# Enc28j60.net
KiCad netlist of a schematic drawn in Altium Designer
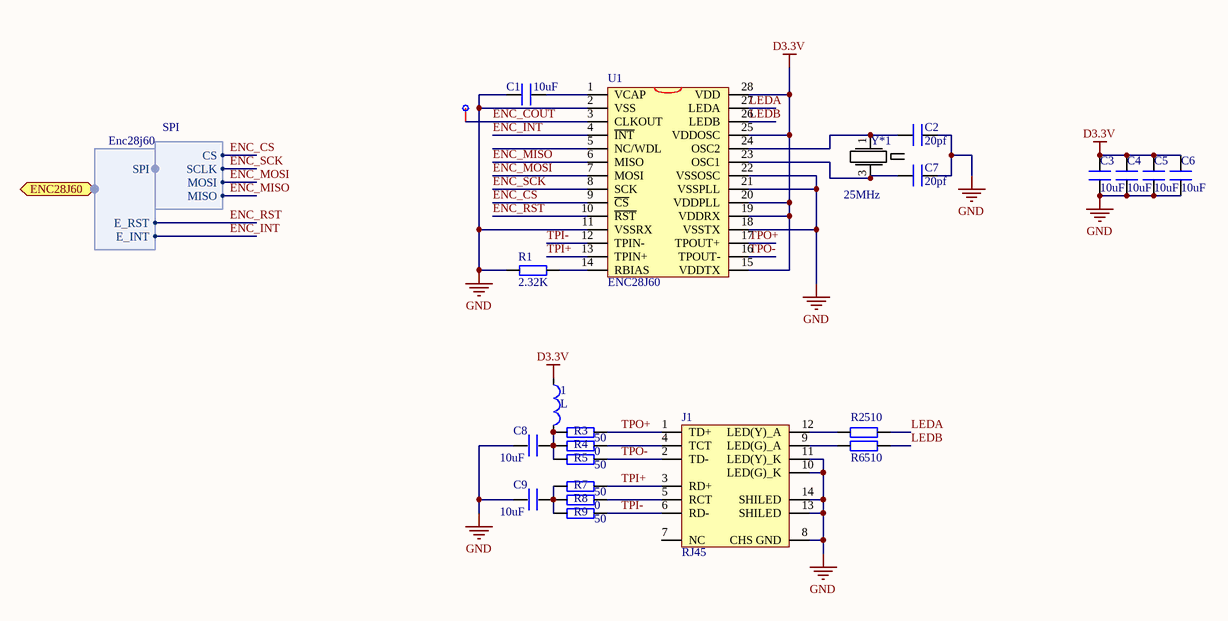
[diagram p0: Enc28j60.SchDoc]

(export (version "E")
  (design (tool "Eeschema 10.0.6"))
  (components
    (comp (ref "*1") (value "Point") (footprint "Point") (libsource (lib "authuir") (part "Point")))
    (comp (ref "1") (value "L") (footprint "0805") (libsource (lib "authuir") (part "L")))
    (comp (ref "C1") (value "10uF") (footprint "0805") (libsource (lib "ENC28J60网络模块封装库") (part "C")))
    (comp (ref "C2") (value "20pf") (footprint "0603P") (libsource (lib "ENC28J60网络模块_SCH") (part "C")))
    (comp (ref "C3") (value "10uF") (footprint "0603P") (libsource (lib "ENC28J60网络模块封装库") (part "C")))
    (comp (ref "C4") (value "10uF") (footprint "0603P") (libsource (lib "ENC28J60网络模块封装库") (part "C")))
    (comp (ref "C5") (value "10uF") (footprint "0603P") (libsource (lib "ENC28J60网络模块封装库") (part "C")))
    (comp (ref "C6") (value "10uF") (footprint "0603P") (libsource (lib "ENC28J60网络模块封装库") (part "C")))
    (comp (ref "C7") (value "20pf") (footprint "0603P") (libsource (lib "ENC28J60网络模块_SCH") (part "C")))
    (comp (ref "C8") (value "10uF") (footprint "0603P") (libsource (lib "ENC28J60网络模块封装库") (part "C")))
    (comp (ref "C9") (value "10uF") (footprint "0603P") (libsource (lib "ENC28J60网络模块封装库") (part "C")))
    (comp (ref "J1")
      (value "RJ45")
      (footprint "HR911105A")
      (libsource (lib "ENC28J60网络模块封装库") (part "HR911105"))
    )
    (comp (ref "R1") (value "2.32K") (footprint "0603P") (libsource (lib "ENC28J60网络模块封装库") (part "R")))
    (comp (ref "R2") (value "510") (footprint "0603P") (libsource (lib "ENC28J60网络模块封装库") (part "R")))
    (comp (ref "R3") (value "50") (footprint "0603P") (libsource (lib "ENC28J60网络模块封装库") (part "R")))
    (comp (ref "R4") (value "0") (footprint "0603P") (libsource (lib "ENC28J60网络模块封装库") (part "R")))
    (comp (ref "R5") (value "50") (footprint "0603P") (libsource (lib "ENC28J60网络模块封装库") (part "R")))
    (comp (ref "R6") (value "510") (footprint "0603P") (libsource (lib "ENC28J60网络模块封装库") (part "R")))
    (comp (ref "R7") (value "50") (footprint "0603P") (libsource (lib "ENC28J60网络模块封装库") (part "R")))
    (comp (ref "R8") (value "0") (footprint "0603P") (libsource (lib "ENC28J60网络模块封装库") (part "R")))
    (comp (ref "R9") (value "50") (footprint "0603P") (libsource (lib "ENC28J60网络模块封装库") (part "R")))
    (comp (ref "U1")
      (value "ENC28J60")
      (footprint "SSOP28")
      (libsource (lib "ENC28J60网络模块_SCH") (part "ENC28J60"))
    )
    (comp (ref "Y*1") (value "25MHz") (footprint "4脚晶振") (libsource (lib "authuir") (part "XTAL_16M")))
  )
  (nets
    (net (code "2") (name "/ENC_COUT") (class "Default")
      (node (ref "*1") (pin "1") (pinfunction "Point_1") (pintype "passive"))
      (node (ref "U1") (pin "3") (pinfunction "CLKOUT_3") (pintype "passive"))
    )
    (net (code "3") (name "/ENC_CS") (class "Default")
      (node (ref "U1") (pin "9") (pinfunction "~{CS}_9") (pintype "passive"))
    )
    (net (code "4") (name "/ENC_INT") (class "Default")
      (node (ref "U1") (pin "4") (pinfunction "~{INT}_4") (pintype "passive"))
    )
    (net (code "5") (name "/ENC_MISO") (class "Default")
      (node (ref "U1") (pin "6") (pinfunction "MISO_6") (pintype "passive"))
    )
    (net (code "6") (name "/ENC_MOSI") (class "Default")
      (node (ref "U1") (pin "7") (pinfunction "MOSI_7") (pintype "passive"))
    )
    (net (code "7") (name "/ENC_RST") (class "Default")
      (node (ref "U1") (pin "10") (pinfunction "~{RST}_10") (pintype "passive"))
    )
    (net (code "8") (name "/ENC_SCK") (class "Default")
      (node (ref "U1") (pin "8") (pinfunction "SCK_8") (pintype "passive"))
    )
    (net (code "9") (name "/LEDA") (class "Default")
      (node (ref "R2") (pin "2") (pintype "passive"))
      (node (ref "U1") (pin "27") (pinfunction "LEDA_27") (pintype "passive"))
    )
    (net (code "10") (name "/LEDB") (class "Default")
      (node (ref "R6") (pin "2") (pintype "passive"))
      (node (ref "U1") (pin "26") (pinfunction "LEDB_26") (pintype "passive"))
    )
    (net (code "11") (name "/TPI+") (class "Default")
      (node (ref "J1") (pin "3") (pinfunction "RD+_3") (pintype "passive"))
      (node (ref "R7") (pin "2") (pintype "passive"))
      (node (ref "U1") (pin "13") (pinfunction "TPIN+_13") (pintype "passive"))
    )
    (net (code "12") (name "/TPI-") (class "Default")
      (node (ref "J1") (pin "6") (pinfunction "RD-_6") (pintype "passive"))
      (node (ref "R9") (pin "2") (pintype "passive"))
      (node (ref "U1") (pin "12") (pinfunction "TPIN-_12") (pintype "passive"))
    )
    (net (code "13") (name "/TPO+") (class "Default")
      (node (ref "J1") (pin "1") (pinfunction "TD+_1") (pintype "passive"))
      (node (ref "R3") (pin "2") (pintype "passive"))
      (node (ref "U1") (pin "17") (pinfunction "TPOUT+_17") (pintype "passive"))
    )
    (net (code "14") (name "/TPO-") (class "Default")
      (node (ref "J1") (pin "2") (pinfunction "TD-_2") (pintype "passive"))
      (node (ref "R5") (pin "2") (pintype "passive"))
      (node (ref "U1") (pin "16") (pinfunction "TPOUT-_16") (pintype "passive"))
    )
    (net (code "16") (name "D3.3V") (class "Default")
      (node (ref "1") (pin "2") (pinfunction "2_2") (pintype "passive"))
      (node (ref "C3") (pin "2") (pintype "passive"))
      (node (ref "C4") (pin "2") (pintype "passive"))
      (node (ref "C5") (pin "2") (pintype "passive"))
      (node (ref "C6") (pin "2") (pintype "passive"))
      (node (ref "U1") (pin "15") (pinfunction "VDDTX_15") (pintype "passive"))
      (node (ref "U1") (pin "19") (pinfunction "VDDRX_19") (pintype "passive"))
      (node (ref "U1") (pin "20") (pinfunction "VDDPLL_20") (pintype "passive"))
      (node (ref "U1") (pin "25") (pinfunction "VDDOSC_25") (pintype "passive"))
      (node (ref "U1") (pin "28") (pinfunction "VDD_28") (pintype "passive"))
    )
    (net (code "17") (name "GND") (class "Default")
      (node (ref "C1") (pin "1") (pintype "passive"))
      (node (ref "C2") (pin "2") (pintype "passive"))
      (node (ref "C3") (pin "1") (pintype "passive"))
      (node (ref "C4") (pin "1") (pintype "passive"))
      (node (ref "C5") (pin "1") (pintype "passive"))
      (node (ref "C6") (pin "1") (pintype "passive"))
      (node (ref "C7") (pin "2") (pintype "passive"))
      (node (ref "C8") (pin "1") (pintype "passive"))
      (node (ref "C9") (pin "1") (pintype "passive"))
      (node (ref "J1") (pin "10") (pinfunction "LED(G)_K_10") (pintype "passive"))
      (node (ref "J1") (pin "11") (pinfunction "LED(Y)_K_11") (pintype "passive"))
      (node (ref "J1") (pin "13") (pinfunction "SHILED_13") (pintype "passive"))
      (node (ref "J1") (pin "14") (pinfunction "SHILED_14") (pintype "passive"))
      (node (ref "J1") (pin "8") (pinfunction "CHS_GND_8") (pintype "passive"))
      (node (ref "R1") (pin "1") (pintype "passive"))
      (node (ref "U1") (pin "11") (pinfunction "VSSRX_11") (pintype "passive"))
      (node (ref "U1") (pin "18") (pinfunction "VSSTX_18") (pintype "passive"))
      (node (ref "U1") (pin "2") (pinfunction "VSS_2") (pintype "passive"))
      (node (ref "U1") (pin "21") (pinfunction "VSSPLL_21") (pintype "passive"))
      (node (ref "U1") (pin "22") (pinfunction "VSSOSC_22") (pintype "passive"))
    )
    (net (code "18") (name "Net-(1-Pad1)") (class "Default")
      (node (ref "1") (pin "1") (pinfunction "1_1") (pintype "passive"))
      (node (ref "C8") (pin "2") (pintype "passive"))
      (node (ref "R3") (pin "1") (pintype "passive"))
      (node (ref "R4") (pin "1") (pintype "passive"))
      (node (ref "R5") (pin "1") (pintype "passive"))
    )
    (net (code "19") (name "Net-(C9-Pad2)") (class "Default")
      (node (ref "C9") (pin "2") (pintype "passive"))
      (node (ref "R7") (pin "1") (pintype "passive"))
      (node (ref "R8") (pin "1") (pintype "passive"))
      (node (ref "R9") (pin "1") (pintype "passive"))
    )
    (net (code "20") (name "Net-(J1-LED(G)_A)") (class "Default")
      (node (ref "J1") (pin "9") (pinfunction "LED(G)_A_9") (pintype "passive"))
      (node (ref "R6") (pin "1") (pintype "passive"))
    )
    (net (code "21") (name "Net-(J1-LED(Y)_A)") (class "Default")
      (node (ref "J1") (pin "12") (pinfunction "LED(Y)_A_12") (pintype "passive"))
      (node (ref "R2") (pin "1") (pintype "passive"))
    )
    (net (code "22") (name "Net-(J1-RCT)") (class "Default")
      (node (ref "J1") (pin "5") (pinfunction "RCT_5") (pintype "passive"))
      (node (ref "R8") (pin "2") (pintype "passive"))
    )
    (net (code "23") (name "Net-(J1-TCT)") (class "Default")
      (node (ref "J1") (pin "4") (pinfunction "TCT_4") (pintype "passive"))
      (node (ref "R4") (pin "2") (pintype "passive"))
    )
    (net (code "24") (name "Net-(U1-OSC1)") (class "Default")
      (node (ref "C7") (pin "1") (pintype "passive"))
      (node (ref "U1") (pin "23") (pinfunction "OSC1_23") (pintype "passive"))
      (node (ref "Y*1") (pin "3") (pinfunction "O_3") (pintype "passive"))
    )
    (net (code "25") (name "Net-(U1-OSC2)") (class "Default")
      (node (ref "C2") (pin "1") (pintype "passive"))
      (node (ref "U1") (pin "24") (pinfunction "OSC2_24") (pintype "passive"))
      (node (ref "Y*1") (pin "1") (pinfunction "O_1") (pintype "passive"))
    )
    (net (code "26") (name "Net-(U1-RBIAS)") (class "Default")
      (node (ref "R1") (pin "2") (pintype "passive"))
      (node (ref "U1") (pin "14") (pinfunction "RBIAS_14") (pintype "passive"))
    )
    (net (code "27") (name "Net-(U1-VCAP)") (class "Default")
      (node (ref "C1") (pin "2") (pintype "passive"))
      (node (ref "U1") (pin "1") (pinfunction "VCAP_1") (pintype "passive"))
    )
    (net (code "28") (name "unconnected-(J1-NC-Pad7)") (class "Default")
      (node (ref "J1") (pin "7") (pinfunction "NC_7") (pintype "passive"))
    )
    (net (code "29") (name "unconnected-(U1-NC{slash}WDL-Pad5)") (class "Default")
      (node (ref "U1") (pin "5") (pinfunction "NC/WDL_5") (pintype "passive"))
    )
    (net (code "30") (name "unconnected-(Y*1-G-Pad2)") (class "Default")
      (node (ref "Y*1") (pin "2") (pinfunction "G_2") (pintype "passive"))
    )
    (net (code "31") (name "unconnected-(Y*1-G-Pad4)") (class "Default")
      (node (ref "Y*1") (pin "4") (pinfunction "G_4") (pintype "passive"))
    )
  )
)
